# INC_ENC_IF.net
KiCad netlist of a schematic drawn in Altium Designer
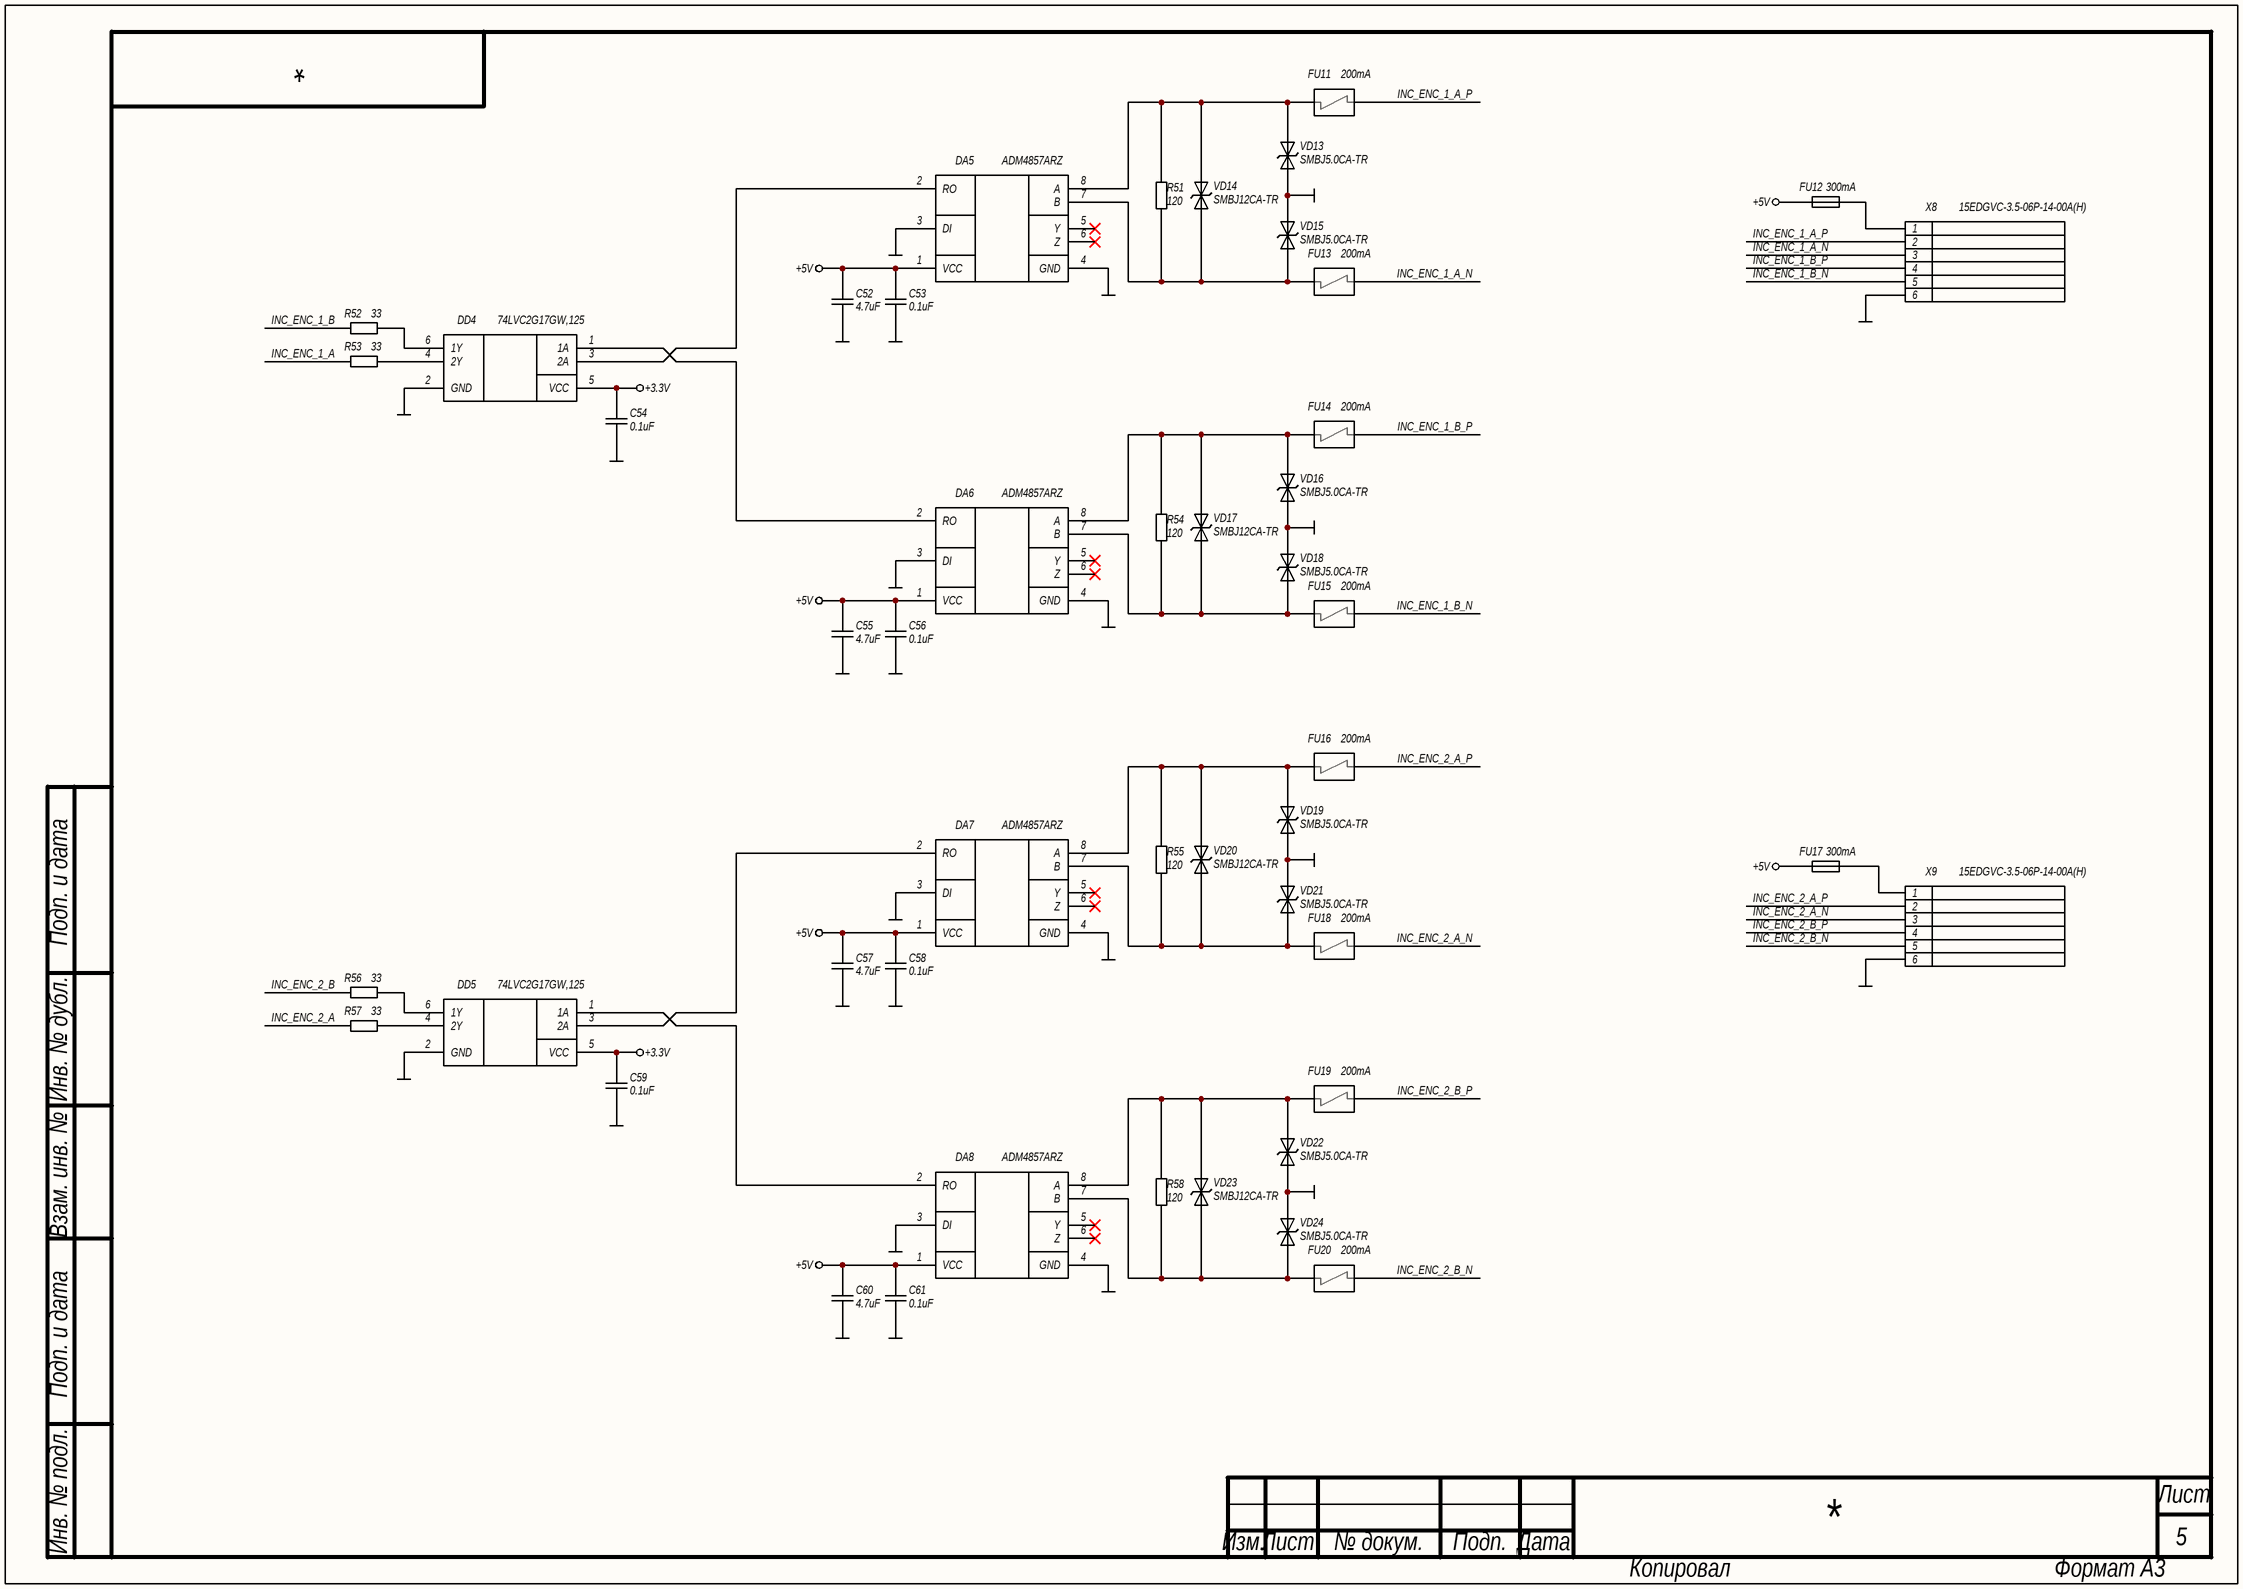
[diagram p0: INC_ENC_IF.SchDoc]

(export (version "E")
  (design (tool "Eeschema 10.0.6"))
  (components
    (comp (ref "C52")
      (value "4.7uF")
      (footprint "C0603N")
      (description "Конденсатор")
      (libsource (lib "Components Library") (part "CAP_FIXED"))
    )
    (comp (ref "C53")
      (value "0.1uF")
      (footprint "C0603N")
      (description "Конденсатор")
      (libsource (lib "Components Library") (part "CAP_FIXED"))
    )
    (comp (ref "C54")
      (value "0.1uF")
      (footprint "C0603N")
      (description "Конденсатор")
      (libsource (lib "Components Library") (part "CAP_FIXED"))
    )
    (comp (ref "C55")
      (value "4.7uF")
      (footprint "C0603N")
      (description "Конденсатор")
      (libsource (lib "Components Library") (part "CAP_FIXED"))
    )
    (comp (ref "C56")
      (value "0.1uF")
      (footprint "C0603N")
      (description "Конденсатор")
      (libsource (lib "Components Library") (part "CAP_FIXED"))
    )
    (comp (ref "C57")
      (value "4.7uF")
      (footprint "C0603N")
      (description "Конденсатор")
      (libsource (lib "Components Library") (part "CAP_FIXED"))
    )
    (comp (ref "C58")
      (value "0.1uF")
      (footprint "C0603N")
      (description "Конденсатор")
      (libsource (lib "Components Library") (part "CAP_FIXED"))
    )
    (comp (ref "C59")
      (value "0.1uF")
      (footprint "C0603N")
      (description "Конденсатор")
      (libsource (lib "Components Library") (part "CAP_FIXED"))
    )
    (comp (ref "C60")
      (value "4.7uF")
      (footprint "C0603N")
      (description "Конденсатор")
      (libsource (lib "Components Library") (part "CAP_FIXED"))
    )
    (comp (ref "C61")
      (value "0.1uF")
      (footprint "C0603N")
      (description "Конденсатор")
      (libsource (lib "Components Library") (part "CAP_FIXED"))
    )
    (comp (ref "DA5")
      (value "ADM4857ARZ")
      (footprint "SOIC8")
      (description "Микросхема интерфейса RS485")
      (libsource (lib "Components Library") (part "ADM4857A"))
    )
    (comp (ref "DA6")
      (value "ADM4857ARZ")
      (footprint "SOIC8")
      (description "Микросхема интерфейса RS485")
      (libsource (lib "Components Library") (part "ADM4857A"))
    )
    (comp (ref "DA7")
      (value "ADM4857ARZ")
      (footprint "SOIC8")
      (description "Микросхема интерфейса RS485")
      (libsource (lib "Components Library") (part "ADM4857A"))
    )
    (comp (ref "DA8")
      (value "ADM4857ARZ")
      (footprint "SOIC8")
      (description "Микросхема интерфейса RS485")
      (libsource (lib "Components Library") (part "ADM4857A"))
    )
    (comp (ref "DD4")
      (value "74LVC2G17GW,125")
      (footprint "SOT363-2")
      (description "Микросхема сдвоенный триггер Шмитта")
      (libsource (lib "Components Library") (part "74LVC2G17"))
    )
    (comp (ref "DD5")
      (value "74LVC2G17GW,125")
      (footprint "SOT363-2")
      (description "Микросхема сдвоенный триггер Шмитта")
      (libsource (lib "Components Library") (part "74LVC2G17"))
    )
    (comp (ref "FU11")
      (value "200mA")
      (footprint "TBU-CA")
      (description "Полупроводниковый предохранитель")
      (libsource (lib "Components Library") (part "FUSE_TBU"))
    )
    (comp (ref "FU12")
      (value "300mA")
      (footprint "MF-MSMF")
      (description "Плавкий предохранитель")
      (libsource (lib "Components Library") (part "FUSE"))
    )
    (comp (ref "FU13")
      (value "200mA")
      (footprint "TBU-CA")
      (description "Полупроводниковый предохранитель")
      (libsource (lib "Components Library") (part "FUSE_TBU"))
    )
    (comp (ref "FU14")
      (value "200mA")
      (footprint "TBU-CA")
      (description "Полупроводниковый предохранитель")
      (libsource (lib "Components Library") (part "FUSE_TBU"))
    )
    (comp (ref "FU15")
      (value "200mA")
      (footprint "TBU-CA")
      (description "Полупроводниковый предохранитель")
      (libsource (lib "Components Library") (part "FUSE_TBU"))
    )
    (comp (ref "FU16")
      (value "200mA")
      (footprint "TBU-CA")
      (description "Полупроводниковый предохранитель")
      (libsource (lib "Components Library") (part "FUSE_TBU"))
    )
    (comp (ref "FU17")
      (value "300mA")
      (footprint "MF-MSMF")
      (description "Плавкий предохранитель")
      (libsource (lib "Components Library") (part "FUSE"))
    )
    (comp (ref "FU18")
      (value "200mA")
      (footprint "TBU-CA")
      (description "Полупроводниковый предохранитель")
      (libsource (lib "Components Library") (part "FUSE_TBU"))
    )
    (comp (ref "FU19")
      (value "200mA")
      (footprint "TBU-CA")
      (description "Полупроводниковый предохранитель")
      (libsource (lib "Components Library") (part "FUSE_TBU"))
    )
    (comp (ref "FU20")
      (value "200mA")
      (footprint "TBU-CA")
      (description "Полупроводниковый предохранитель")
      (libsource (lib "Components Library") (part "FUSE_TBU"))
    )
    (comp (ref "R51")
      (value "120")
      (footprint "R0805N")
      (description "Резистор")
      (libsource (lib "") (part "RES_FIXED_1"))
    )
    (comp (ref "R52")
      (value "33")
      (footprint "R0603N")
      (description "Резистор")
      (libsource (lib "Components Library") (part "RES_FIXED"))
    )
    (comp (ref "R53")
      (value "33")
      (footprint "R0603N")
      (description "Резистор")
      (libsource (lib "Components Library") (part "RES_FIXED"))
    )
    (comp (ref "R54")
      (value "120")
      (footprint "R0805N")
      (description "Резистор")
      (libsource (lib "") (part "RES_FIXED_1"))
    )
    (comp (ref "R55")
      (value "120")
      (footprint "R0805N")
      (description "Резистор")
      (libsource (lib "") (part "RES_FIXED_1"))
    )
    (comp (ref "R56")
      (value "33")
      (footprint "R0603N")
      (description "Резистор")
      (libsource (lib "Components Library") (part "RES_FIXED"))
    )
    (comp (ref "R57")
      (value "33")
      (footprint "R0603N")
      (description "Резистор")
      (libsource (lib "Components Library") (part "RES_FIXED"))
    )
    (comp (ref "R58")
      (value "120")
      (footprint "R0805N")
      (description "Резистор")
      (libsource (lib "") (part "RES_FIXED_1"))
    )
    (comp (ref "VD13")
      (value "SMBJ5.0CA-TR")
      (footprint "SMB")
      (description "TVS диод двунаправленный")
      (libsource (lib "Components Library") (part "TVS_BIDIR"))
    )
    (comp (ref "VD14")
      (value "SMBJ12CA-TR")
      (footprint "SMB")
      (description "TVS диод двунаправленный")
      (libsource (lib "Components Library") (part "TVS_BIDIR"))
    )
    (comp (ref "VD15")
      (value "SMBJ5.0CA-TR")
      (footprint "SMB")
      (description "TVS диод двунаправленный")
      (libsource (lib "Components Library") (part "TVS_BIDIR"))
    )
    (comp (ref "VD16")
      (value "SMBJ5.0CA-TR")
      (footprint "SMB")
      (description "TVS диод двунаправленный")
      (libsource (lib "Components Library") (part "TVS_BIDIR"))
    )
    (comp (ref "VD17")
      (value "SMBJ12CA-TR")
      (footprint "SMB")
      (description "TVS диод двунаправленный")
      (libsource (lib "Components Library") (part "TVS_BIDIR"))
    )
    (comp (ref "VD18")
      (value "SMBJ5.0CA-TR")
      (footprint "SMB")
      (description "TVS диод двунаправленный")
      (libsource (lib "Components Library") (part "TVS_BIDIR"))
    )
    (comp (ref "VD19")
      (value "SMBJ5.0CA-TR")
      (footprint "SMB")
      (description "TVS диод двунаправленный")
      (libsource (lib "Components Library") (part "TVS_BIDIR"))
    )
    (comp (ref "VD20")
      (value "SMBJ12CA-TR")
      (footprint "SMB")
      (description "TVS диод двунаправленный")
      (libsource (lib "Components Library") (part "TVS_BIDIR"))
    )
    (comp (ref "VD21")
      (value "SMBJ5.0CA-TR")
      (footprint "SMB")
      (description "TVS диод двунаправленный")
      (libsource (lib "Components Library") (part "TVS_BIDIR"))
    )
    (comp (ref "VD22")
      (value "SMBJ5.0CA-TR")
      (footprint "SMB")
      (description "TVS диод двунаправленный")
      (libsource (lib "Components Library") (part "TVS_BIDIR"))
    )
    (comp (ref "VD23")
      (value "SMBJ12CA-TR")
      (footprint "SMB")
      (description "TVS диод двунаправленный")
      (libsource (lib "Components Library") (part "TVS_BIDIR"))
    )
    (comp (ref "VD24")
      (value "SMBJ5.0CA-TR")
      (footprint "SMB")
      (description "TVS диод двунаправленный")
      (libsource (lib "Components Library") (part "TVS_BIDIR"))
    )
    (comp (ref "X8")
      (value "15EDGVC-3.5-06P-14-00A(H)")
      (footprint "15EDGVC-3.5-06P-14-00A(H)")
      (description "Разъем, 6 контактов")
      (libsource (lib "Components Library") (part "Connector 6"))
    )
    (comp (ref "X9")
      (value "15EDGVC-3.5-06P-14-00A(H)")
      (footprint "15EDGVC-3.5-06P-14-00A(H)")
      (description "Разъем, 6 контактов")
      (libsource (lib "Components Library") (part "Connector 6"))
    )
  )
  (nets
    (net (code "1") (name "+3.3V") (class "Default")
      (node (ref "C54") (pin "2") (pinfunction "2_2") (pintype "passive"))
      (node (ref "C59") (pin "2") (pinfunction "2_2") (pintype "passive"))
      (node (ref "DD4") (pin "5") (pinfunction "VCC_5") (pintype "power_in"))
      (node (ref "DD5") (pin "5") (pinfunction "VCC_5") (pintype "power_in"))
    )
    (net (code "2") (name "+5V") (class "Default")
      (node (ref "C52") (pin "2") (pinfunction "2_2") (pintype "passive"))
      (node (ref "C53") (pin "2") (pinfunction "2_2") (pintype "passive"))
      (node (ref "C55") (pin "2") (pinfunction "2_2") (pintype "passive"))
      (node (ref "C56") (pin "2") (pinfunction "2_2") (pintype "passive"))
      (node (ref "C57") (pin "2") (pinfunction "2_2") (pintype "passive"))
      (node (ref "C58") (pin "2") (pinfunction "2_2") (pintype "passive"))
      (node (ref "C60") (pin "2") (pinfunction "2_2") (pintype "passive"))
      (node (ref "C61") (pin "2") (pinfunction "2_2") (pintype "passive"))
      (node (ref "DA5") (pin "1") (pinfunction "VCC_1") (pintype "power_in"))
      (node (ref "DA6") (pin "1") (pinfunction "VCC_1") (pintype "power_in"))
      (node (ref "DA7") (pin "1") (pinfunction "VCC_1") (pintype "power_in"))
      (node (ref "DA8") (pin "1") (pinfunction "VCC_1") (pintype "power_in"))
      (node (ref "FU12") (pin "1") (pinfunction "1_1") (pintype "passive"))
      (node (ref "FU17") (pin "1") (pinfunction "1_1") (pintype "passive"))
    )
    (net (code "3") (name "/INC_ENC_1_A") (class "Default")
      (node (ref "R53") (pin "2") (pinfunction "2_2") (pintype "passive"))
    )
    (net (code "4") (name "/INC_ENC_1_A_N") (class "Default")
      (node (ref "FU13") (pin "3") (pinfunction "IN/OUT_3") (pintype "passive"))
      (node (ref "X8") (pin "3") (pinfunction "3_3") (pintype "power_in"))
    )
    (net (code "5") (name "/INC_ENC_1_A_P") (class "Default")
      (node (ref "FU11") (pin "3") (pinfunction "IN/OUT_3") (pintype "passive"))
      (node (ref "X8") (pin "2") (pinfunction "2_2") (pintype "power_in"))
    )
    (net (code "6") (name "/INC_ENC_1_B") (class "Default")
      (node (ref "R52") (pin "2") (pinfunction "2_2") (pintype "passive"))
    )
    (net (code "7") (name "/INC_ENC_1_B_N") (class "Default")
      (node (ref "FU15") (pin "3") (pinfunction "IN/OUT_3") (pintype "passive"))
      (node (ref "X8") (pin "5") (pinfunction "5_5") (pintype "power_in"))
    )
    (net (code "8") (name "/INC_ENC_1_B_P") (class "Default")
      (node (ref "FU14") (pin "3") (pinfunction "IN/OUT_3") (pintype "passive"))
      (node (ref "X8") (pin "4") (pinfunction "4_4") (pintype "power_in"))
    )
    (net (code "9") (name "/INC_ENC_2_A") (class "Default")
      (node (ref "R57") (pin "2") (pinfunction "2_2") (pintype "passive"))
    )
    (net (code "10") (name "/INC_ENC_2_A_N") (class "Default")
      (node (ref "FU18") (pin "3") (pinfunction "IN/OUT_3") (pintype "passive"))
      (node (ref "X9") (pin "3") (pinfunction "3_3") (pintype "power_in"))
    )
    (net (code "11") (name "/INC_ENC_2_A_P") (class "Default")
      (node (ref "FU16") (pin "3") (pinfunction "IN/OUT_3") (pintype "passive"))
      (node (ref "X9") (pin "2") (pinfunction "2_2") (pintype "power_in"))
    )
    (net (code "12") (name "/INC_ENC_2_B") (class "Default")
      (node (ref "R56") (pin "2") (pinfunction "2_2") (pintype "passive"))
    )
    (net (code "13") (name "/INC_ENC_2_B_N") (class "Default")
      (node (ref "FU20") (pin "3") (pinfunction "IN/OUT_3") (pintype "passive"))
      (node (ref "X9") (pin "5") (pinfunction "5_5") (pintype "power_in"))
    )
    (net (code "14") (name "/INC_ENC_2_B_P") (class "Default")
      (node (ref "FU19") (pin "3") (pinfunction "IN/OUT_3") (pintype "passive"))
      (node (ref "X9") (pin "4") (pinfunction "4_4") (pintype "power_in"))
    )
    (net (code "15") (name "GND") (class "Default")
      (node (ref "C52") (pin "1") (pinfunction "1_1") (pintype "passive"))
      (node (ref "C53") (pin "1") (pinfunction "1_1") (pintype "passive"))
      (node (ref "C54") (pin "1") (pinfunction "1_1") (pintype "passive"))
      (node (ref "C55") (pin "1") (pinfunction "1_1") (pintype "passive"))
      (node (ref "C56") (pin "1") (pinfunction "1_1") (pintype "passive"))
      (node (ref "C57") (pin "1") (pinfunction "1_1") (pintype "passive"))
      (node (ref "C58") (pin "1") (pinfunction "1_1") (pintype "passive"))
      (node (ref "C59") (pin "1") (pinfunction "1_1") (pintype "passive"))
      (node (ref "C60") (pin "1") (pinfunction "1_1") (pintype "passive"))
      (node (ref "C61") (pin "1") (pinfunction "1_1") (pintype "passive"))
      (node (ref "DA5") (pin "3") (pinfunction "DI_3") (pintype "power_in"))
      (node (ref "DA5") (pin "4") (pinfunction "GND_4") (pintype "power_in"))
      (node (ref "DA6") (pin "3") (pinfunction "DI_3") (pintype "power_in"))
      (node (ref "DA6") (pin "4") (pinfunction "GND_4") (pintype "power_in"))
      (node (ref "DA7") (pin "3") (pinfunction "DI_3") (pintype "power_in"))
      (node (ref "DA7") (pin "4") (pinfunction "GND_4") (pintype "power_in"))
      (node (ref "DA8") (pin "3") (pinfunction "DI_3") (pintype "power_in"))
      (node (ref "DA8") (pin "4") (pinfunction "GND_4") (pintype "power_in"))
      (node (ref "DD4") (pin "2") (pinfunction "GND_2") (pintype "power_in"))
      (node (ref "DD5") (pin "2") (pinfunction "GND_2") (pintype "power_in"))
      (node (ref "VD13") (pin "2") (pinfunction "A2_2") (pintype "passive"))
      (node (ref "VD15") (pin "2") (pinfunction "A2_2") (pintype "passive"))
      (node (ref "VD16") (pin "2") (pinfunction "A2_2") (pintype "passive"))
      (node (ref "VD18") (pin "2") (pinfunction "A2_2") (pintype "passive"))
      (node (ref "VD19") (pin "2") (pinfunction "A2_2") (pintype "passive"))
      (node (ref "VD21") (pin "2") (pinfunction "A2_2") (pintype "passive"))
      (node (ref "VD22") (pin "2") (pinfunction "A2_2") (pintype "passive"))
      (node (ref "VD24") (pin "2") (pinfunction "A2_2") (pintype "passive"))
      (node (ref "X8") (pin "6") (pinfunction "6_6") (pintype "power_in"))
      (node (ref "X9") (pin "6") (pinfunction "6_6") (pintype "power_in"))
    )
    (net (code "16") (name "Net-(DA5-A)") (class "Default")
      (node (ref "DA5") (pin "8") (pinfunction "A_8") (pintype "power_in"))
      (node (ref "FU11") (pin "1") (pinfunction "IN/OUT_1") (pintype "passive"))
      (node (ref "R51") (pin "1") (pinfunction "1_1") (pintype "passive"))
      (node (ref "VD13") (pin "1") (pinfunction "A1_1") (pintype "passive"))
      (node (ref "VD14") (pin "1") (pinfunction "A1_1") (pintype "passive"))
    )
    (net (code "17") (name "Net-(DA5-B)") (class "Default")
      (node (ref "DA5") (pin "7") (pinfunction "B_7") (pintype "power_in"))
      (node (ref "FU13") (pin "1") (pinfunction "IN/OUT_1") (pintype "passive"))
      (node (ref "R51") (pin "2") (pinfunction "2_2") (pintype "passive"))
      (node (ref "VD14") (pin "2") (pinfunction "A2_2") (pintype "passive"))
      (node (ref "VD15") (pin "1") (pinfunction "A1_1") (pintype "passive"))
    )
    (net (code "18") (name "Net-(DA5-RO)") (class "Default")
      (node (ref "DA5") (pin "2") (pinfunction "RO_2") (pintype "power_in"))
      (node (ref "DD4") (pin "3") (pinfunction "2A_3") (pintype "power_in"))
    )
    (net (code "19") (name "Net-(DA6-A)") (class "Default")
      (node (ref "DA6") (pin "8") (pinfunction "A_8") (pintype "power_in"))
      (node (ref "FU14") (pin "1") (pinfunction "IN/OUT_1") (pintype "passive"))
      (node (ref "R54") (pin "1") (pinfunction "1_1") (pintype "passive"))
      (node (ref "VD16") (pin "1") (pinfunction "A1_1") (pintype "passive"))
      (node (ref "VD17") (pin "1") (pinfunction "A1_1") (pintype "passive"))
    )
    (net (code "20") (name "Net-(DA6-B)") (class "Default")
      (node (ref "DA6") (pin "7") (pinfunction "B_7") (pintype "power_in"))
      (node (ref "FU15") (pin "1") (pinfunction "IN/OUT_1") (pintype "passive"))
      (node (ref "R54") (pin "2") (pinfunction "2_2") (pintype "passive"))
      (node (ref "VD17") (pin "2") (pinfunction "A2_2") (pintype "passive"))
      (node (ref "VD18") (pin "1") (pinfunction "A1_1") (pintype "passive"))
    )
    (net (code "21") (name "Net-(DA6-RO)") (class "Default")
      (node (ref "DA6") (pin "2") (pinfunction "RO_2") (pintype "power_in"))
      (node (ref "DD4") (pin "1") (pinfunction "1A_1") (pintype "power_in"))
    )
    (net (code "22") (name "Net-(DA7-A)") (class "Default")
      (node (ref "DA7") (pin "8") (pinfunction "A_8") (pintype "power_in"))
      (node (ref "FU16") (pin "1") (pinfunction "IN/OUT_1") (pintype "passive"))
      (node (ref "R55") (pin "1") (pinfunction "1_1") (pintype "passive"))
      (node (ref "VD19") (pin "1") (pinfunction "A1_1") (pintype "passive"))
      (node (ref "VD20") (pin "1") (pinfunction "A1_1") (pintype "passive"))
    )
    (net (code "23") (name "Net-(DA7-B)") (class "Default")
      (node (ref "DA7") (pin "7") (pinfunction "B_7") (pintype "power_in"))
      (node (ref "FU18") (pin "1") (pinfunction "IN/OUT_1") (pintype "passive"))
      (node (ref "R55") (pin "2") (pinfunction "2_2") (pintype "passive"))
      (node (ref "VD20") (pin "2") (pinfunction "A2_2") (pintype "passive"))
      (node (ref "VD21") (pin "1") (pinfunction "A1_1") (pintype "passive"))
    )
    (net (code "24") (name "Net-(DA7-RO)") (class "Default")
      (node (ref "DA7") (pin "2") (pinfunction "RO_2") (pintype "power_in"))
      (node (ref "DD5") (pin "3") (pinfunction "2A_3") (pintype "power_in"))
    )
    (net (code "25") (name "Net-(DA8-A)") (class "Default")
      (node (ref "DA8") (pin "8") (pinfunction "A_8") (pintype "power_in"))
      (node (ref "FU19") (pin "1") (pinfunction "IN/OUT_1") (pintype "passive"))
      (node (ref "R58") (pin "1") (pinfunction "1_1") (pintype "passive"))
      (node (ref "VD22") (pin "1") (pinfunction "A1_1") (pintype "passive"))
      (node (ref "VD23") (pin "1") (pinfunction "A1_1") (pintype "passive"))
    )
    (net (code "26") (name "Net-(DA8-B)") (class "Default")
      (node (ref "DA8") (pin "7") (pinfunction "B_7") (pintype "power_in"))
      (node (ref "FU20") (pin "1") (pinfunction "IN/OUT_1") (pintype "passive"))
      (node (ref "R58") (pin "2") (pinfunction "2_2") (pintype "passive"))
      (node (ref "VD23") (pin "2") (pinfunction "A2_2") (pintype "passive"))
      (node (ref "VD24") (pin "1") (pinfunction "A1_1") (pintype "passive"))
    )
    (net (code "27") (name "Net-(DA8-RO)") (class "Default")
      (node (ref "DA8") (pin "2") (pinfunction "RO_2") (pintype "power_in"))
      (node (ref "DD5") (pin "1") (pinfunction "1A_1") (pintype "power_in"))
    )
    (net (code "28") (name "Net-(DD4-1Y)") (class "Default")
      (node (ref "DD4") (pin "6") (pinfunction "1Y_6") (pintype "power_in"))
      (node (ref "R52") (pin "1") (pinfunction "1_1") (pintype "passive"))
    )
    (net (code "29") (name "Net-(DD4-2Y)") (class "Default")
      (node (ref "DD4") (pin "4") (pinfunction "2Y_4") (pintype "power_in"))
      (node (ref "R53") (pin "1") (pinfunction "1_1") (pintype "passive"))
    )
    (net (code "30") (name "Net-(DD5-1Y)") (class "Default")
      (node (ref "DD5") (pin "6") (pinfunction "1Y_6") (pintype "power_in"))
      (node (ref "R56") (pin "1") (pinfunction "1_1") (pintype "passive"))
    )
    (net (code "31") (name "Net-(DD5-2Y)") (class "Default")
      (node (ref "DD5") (pin "4") (pinfunction "2Y_4") (pintype "power_in"))
      (node (ref "R57") (pin "1") (pinfunction "1_1") (pintype "passive"))
    )
    (net (code "32") (name "Net-(FU12-Pad2)") (class "Default")
      (node (ref "FU12") (pin "2") (pinfunction "2_2") (pintype "passive"))
      (node (ref "X8") (pin "1") (pinfunction "1_1") (pintype "power_in"))
    )
    (net (code "33") (name "Net-(FU17-Pad2)") (class "Default")
      (node (ref "FU17") (pin "2") (pinfunction "2_2") (pintype "passive"))
      (node (ref "X9") (pin "1") (pinfunction "1_1") (pintype "power_in"))
    )
    (net (code "34") (name "unconnected-(DA5-Y-Pad5)") (class "Default")
      (node (ref "DA5") (pin "5") (pinfunction "Y_5") (pintype "power_in+no_connect"))
    )
    (net (code "35") (name "unconnected-(DA5-Z-Pad6)") (class "Default")
      (node (ref "DA5") (pin "6") (pinfunction "Z_6") (pintype "power_in+no_connect"))
    )
    (net (code "36") (name "unconnected-(DA6-Y-Pad5)") (class "Default")
      (node (ref "DA6") (pin "5") (pinfunction "Y_5") (pintype "power_in+no_connect"))
    )
    (net (code "37") (name "unconnected-(DA6-Z-Pad6)") (class "Default")
      (node (ref "DA6") (pin "6") (pinfunction "Z_6") (pintype "power_in+no_connect"))
    )
    (net (code "38") (name "unconnected-(DA7-Y-Pad5)") (class "Default")
      (node (ref "DA7") (pin "5") (pinfunction "Y_5") (pintype "power_in+no_connect"))
    )
    (net (code "39") (name "unconnected-(DA7-Z-Pad6)") (class "Default")
      (node (ref "DA7") (pin "6") (pinfunction "Z_6") (pintype "power_in+no_connect"))
    )
    (net (code "40") (name "unconnected-(DA8-Y-Pad5)") (class "Default")
      (node (ref "DA8") (pin "5") (pinfunction "Y_5") (pintype "power_in+no_connect"))
    )
    (net (code "41") (name "unconnected-(DA8-Z-Pad6)") (class "Default")
      (node (ref "DA8") (pin "6") (pinfunction "Z_6") (pintype "power_in+no_connect"))
    )
  )
)
